# CANIso.net
KiCad netlist of a schematic drawn in EAGLE
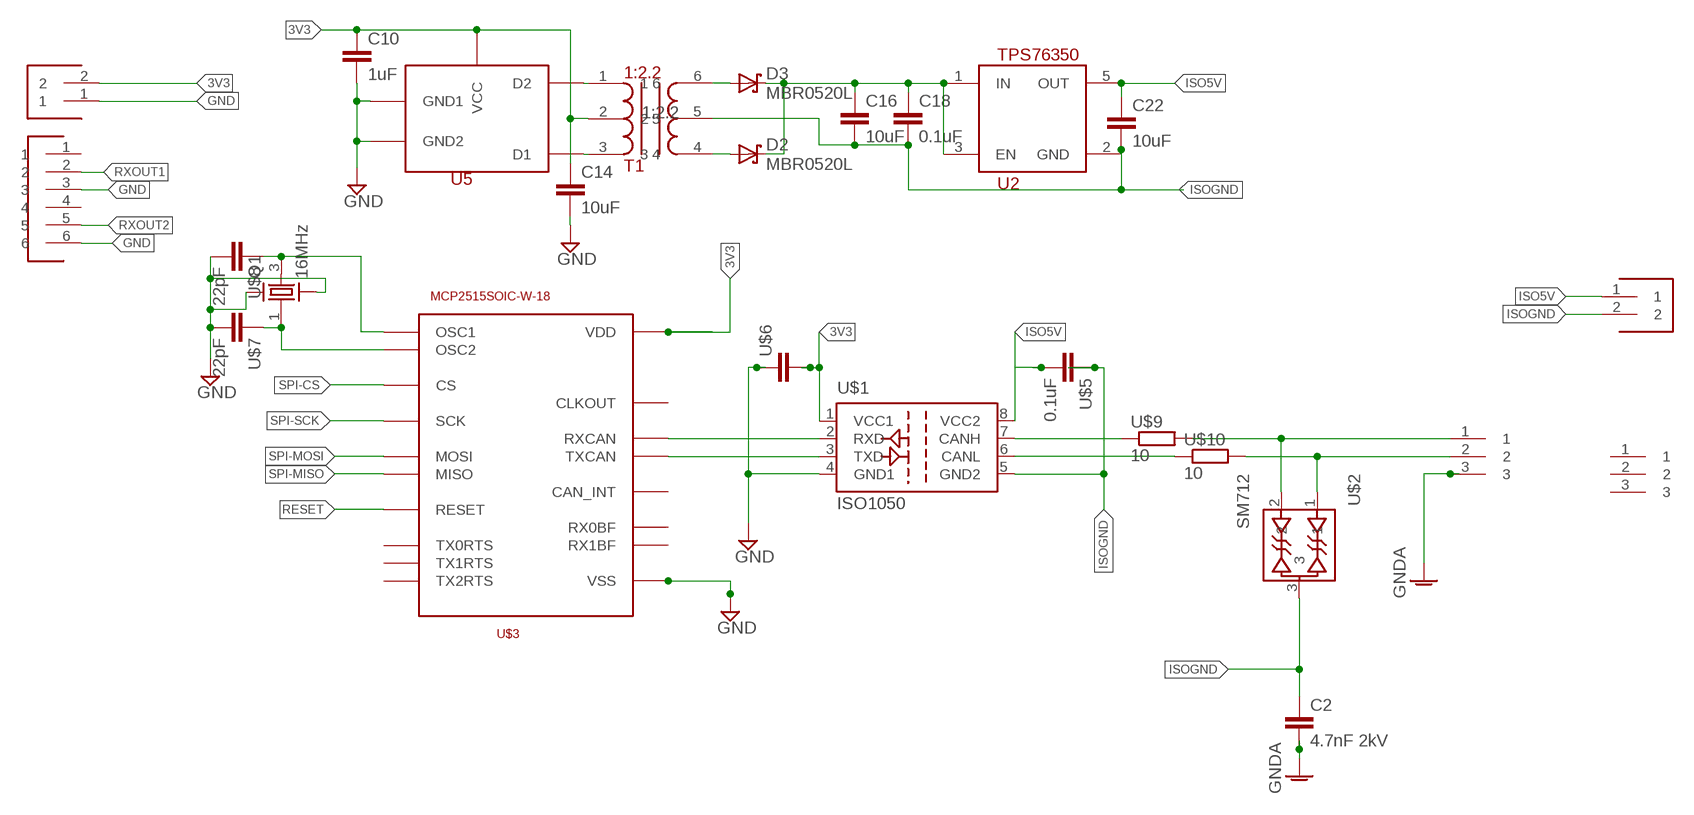
[diagram p0: schematic, sheet 1]

(export (version "E")
  (design (tool "Eeschema 10.0.6"))
  (components
    (comp (ref "C2")
      (value "4.7nF 2kV")
      (footprint "eagle-import:0805")
      (libsource (lib "eagle-import") (part "CAP0805"))
    )
    (comp (ref "C10")
      (value "1uF")
      (footprint "eagle-import:0805")
      (libsource (lib "eagle-import") (part "CAP0805"))
    )
    (comp (ref "C14")
      (value "10uF")
      (footprint "eagle-import:0805")
      (libsource (lib "eagle-import") (part "CAP0805"))
    )
    (comp (ref "C16")
      (value "10uF")
      (footprint "eagle-import:0805")
      (libsource (lib "eagle-import") (part "CAP0805"))
    )
    (comp (ref "C18")
      (value "0.1uF")
      (footprint "eagle-import:0805")
      (libsource (lib "eagle-import") (part "CAP0805"))
    )
    (comp (ref "C22")
      (value "10uF")
      (footprint "eagle-import:0805")
      (libsource (lib "eagle-import") (part "CAP0805"))
    )
    (comp (ref "D2")
      (value "MBR0520L")
      (footprint "eagle-import:SOD123")
      (libsource (lib "eagle-import") (part "MBR0520L"))
    )
    (comp (ref "D3")
      (value "MBR0520L")
      (footprint "eagle-import:SOD123")
      (libsource (lib "eagle-import") (part "MBR0520L"))
    )
    (comp (ref "J1")
      (value "CON-2STD-2.54")
      (footprint "eagle-import:CON-2")
      (libsource (lib "eagle-import") (part "CON-2STD-2.54"))
    )
    (comp (ref "J3")
      (value "CON-2STD-2.54")
      (footprint "eagle-import:CON-2")
      (libsource (lib "eagle-import") (part "CON-2STD-2.54"))
    )
    (comp (ref "J4")
      (value "CON-6")
      (footprint "eagle-import:CON-6")
      (libsource (lib "eagle-import") (part "CON-6"))
    )
    (comp (ref "Q1")
      (value "16MHz")
      (footprint "eagle-import:ABM3B")
      (libsource (lib "eagle-import") (part "ABM3B"))
    )
    (comp (ref "T1")
      (value "1:2.2")
      (footprint "eagle-import:WE_TRANSFORMER")
      (fields (field (name "TURNS") "1:2.2"))
      (libsource (lib "eagle-import") (part "WE-PP-ISO-TRANSFORMER760390013"))
    )
    (comp (ref "U$1")
      (value "ISO1050")
      (footprint "eagle-import:DUB")
      (libsource (lib "eagle-import") (part "ISO1050"))
    )
    (comp (ref "U$2")
      (value "SM712")
      (footprint "eagle-import:SOT23-3L")
      (libsource (lib "eagle-import") (part "SM712"))
    )
    (comp (ref "U$3")
      (value "MCP2515SOIC-W-18")
      (footprint "eagle-import:SOIC-W-18")
      (libsource (lib "eagle-import") (part "MCP2515SOIC-W-18"))
    )
    (comp (ref "U$4")
      (value "CON-3")
      (footprint "eagle-import:CON-3")
      (libsource (lib "eagle-import") (part "CON-3"))
    )
    (comp (ref "U$5")
      (value "0.1uF")
      (footprint "eagle-import:0805")
      (libsource (lib "eagle-import") (part "CAP0805"))
    )
    (comp (ref "U$6")
      (value "CAP0805")
      (footprint "eagle-import:0805")
      (libsource (lib "eagle-import") (part "CAP0805"))
    )
    (comp (ref "U$7")
      (value "22pF")
      (footprint "eagle-import:0805")
      (libsource (lib "eagle-import") (part "CAP0805"))
    )
    (comp (ref "U$8")
      (value "22pF")
      (footprint "eagle-import:0805")
      (libsource (lib "eagle-import") (part "CAP0805"))
    )
    (comp (ref "U$9")
      (value "10")
      (footprint "eagle-import:0805")
      (libsource (lib "eagle-import") (part "RES0805"))
    )
    (comp (ref "U$10")
      (value "10")
      (footprint "eagle-import:0805")
      (libsource (lib "eagle-import") (part "RES0805"))
    )
    (comp (ref "U$11")
      (value "CON-3")
      (footprint "eagle-import:CON-3")
      (libsource (lib "eagle-import") (part "CON-3"))
    )
    (comp (ref "U2")
      (value "TPS76350")
      (footprint "eagle-import:SOT23-5L")
      (libsource (lib "eagle-import") (part "TPS76350"))
    )
    (comp (ref "U5")
      (value "SN6501DBVT")
      (footprint "eagle-import:SOT23-5L")
      (libsource (lib "eagle-import") (part "SN6501DBVT"))
    )
  )
  (nets
    (net (code "1") (name "3V3") (class "Default")
      (node (ref "C10") (pin "1") (pinfunction "1_1") (pintype "passive"))
      (node (ref "C14") (pin "1") (pinfunction "1_1") (pintype "passive"))
      (node (ref "J1") (pin "2") (pinfunction "2_2") (pintype "bidirectional"))
      (node (ref "T1") (pin "2") (pinfunction "2_2") (pintype "input"))
      (node (ref "U$1") (pin "1") (pinfunction "VCC1_1") (pintype "power_in"))
      (node (ref "U$3") (pin "18") (pinfunction "VDD_18") (pintype "power_in"))
      (node (ref "U$6") (pin "2") (pinfunction "2_2") (pintype "passive"))
      (node (ref "U5") (pin "2") (pinfunction "VCC_2") (pintype "bidirectional"))
    )
    (net (code "2") (name "GND") (class "Default")
      (node (ref "C10") (pin "2") (pinfunction "2_2") (pintype "passive"))
      (node (ref "C14") (pin "2") (pinfunction "2_2") (pintype "passive"))
      (node (ref "J1") (pin "1") (pinfunction "1_1") (pintype "bidirectional"))
      (node (ref "J4") (pin "3") (pinfunction "3_3") (pintype "bidirectional"))
      (node (ref "J4") (pin "6") (pinfunction "6_6") (pintype "bidirectional"))
      (node (ref "Q1") (pin "2") (pinfunction "GND_2") (pintype "bidirectional"))
      (node (ref "Q1") (pin "4") (pinfunction "GND2_4") (pintype "bidirectional"))
      (node (ref "U$1") (pin "4") (pinfunction "GND1_4") (pintype "power_in"))
      (node (ref "U$3") (pin "9") (pinfunction "VSS_9") (pintype "power_in"))
      (node (ref "U$6") (pin "1") (pinfunction "1_1") (pintype "passive"))
      (node (ref "U$7") (pin "2") (pinfunction "2_2") (pintype "passive"))
      (node (ref "U$8") (pin "2") (pinfunction "2_2") (pintype "passive"))
      (node (ref "U5") (pin "4") (pinfunction "GND1_4") (pintype "bidirectional"))
      (node (ref "U5") (pin "5") (pinfunction "GND2_5") (pintype "bidirectional"))
    )
    (net (code "3") (name "GNDA") (class "Default")
      (node (ref "C2") (pin "2") (pinfunction "2_2") (pintype "passive"))
      (node (ref "U$4") (pin "3") (pinfunction "3_3") (pintype "bidirectional"))
    )
    (net (code "4") (name "ISO5V") (class "Default")
      (node (ref "C22") (pin "1") (pinfunction "1_1") (pintype "passive"))
      (node (ref "J3") (pin "1") (pinfunction "1_1") (pintype "bidirectional"))
      (node (ref "U$1") (pin "8") (pinfunction "VCC2_8") (pintype "power_in"))
      (node (ref "U2") (pin "5") (pinfunction "OUT_5") (pintype "bidirectional"))
    )
    (net (code "5") (name "ISOGND") (class "Default")
      (node (ref "C16") (pin "2") (pinfunction "2_2") (pintype "passive"))
      (node (ref "C18") (pin "2") (pinfunction "2_2") (pintype "passive"))
      (node (ref "C2") (pin "1") (pinfunction "1_1") (pintype "passive"))
      (node (ref "C22") (pin "2") (pinfunction "2_2") (pintype "passive"))
      (node (ref "J3") (pin "2") (pinfunction "2_2") (pintype "bidirectional"))
      (node (ref "T1") (pin "5") (pinfunction "5_5") (pintype "passive"))
      (node (ref "U$1") (pin "5") (pinfunction "GND2_5") (pintype "power_in"))
      (node (ref "U$2") (pin "3") (pinfunction "3_3") (pintype "output"))
      (node (ref "U$5") (pin "1") (pinfunction "1_1") (pintype "passive"))
      (node (ref "U2") (pin "2") (pinfunction "GND_2") (pintype "bidirectional"))
    )
    (net (code "6") (name "Net-(D2-PadA)") (class "Default")
      (node (ref "D2") (pin "A") (pinfunction "A_A") (pintype "passive"))
      (node (ref "T1") (pin "4") (pinfunction "4_4") (pintype "passive"))
    )
    (net (code "7") (name "Net-(D3-PadA)") (class "Default")
      (node (ref "D3") (pin "A") (pinfunction "A_A") (pintype "passive"))
      (node (ref "T1") (pin "6") (pinfunction "6_6") (pintype "passive"))
    )
    (net (code "8") (name "Net-(Q1-2)") (class "Default")
      (node (ref "Q1") (pin "3") (pinfunction "2_3") (pintype "passive"))
      (node (ref "U$3") (pin "8") (pinfunction "OSC1_8") (pintype "bidirectional"))
      (node (ref "U$8") (pin "1") (pinfunction "1_1") (pintype "passive"))
    )
    (net (code "9") (name "Net-(U$1-CANH)") (class "Default")
      (node (ref "U$1") (pin "7") (pinfunction "CANH_7") (pintype "output"))
      (node (ref "U$9") (pin "1") (pinfunction "1_1") (pintype "passive"))
    )
    (net (code "10") (name "Net-(U$1-CANL)") (class "Default")
      (node (ref "U$1") (pin "6") (pinfunction "CANL_6") (pintype "output"))
      (node (ref "U$10") (pin "1") (pinfunction "1_1") (pintype "passive"))
    )
    (net (code "11") (name "Net-(U$1-RXD)") (class "Default")
      (node (ref "U$1") (pin "2") (pinfunction "RXD_2") (pintype "input"))
      (node (ref "U$3") (pin "2") (pinfunction "RXCAN_2") (pintype "bidirectional"))
    )
    (net (code "12") (name "Net-(U$1-TXD)") (class "Default")
      (node (ref "U$1") (pin "3") (pinfunction "TXD_3") (pintype "input"))
      (node (ref "U$3") (pin "1") (pinfunction "TXCAN_1") (pintype "bidirectional"))
    )
    (net (code "13") (name "Net-(U$2-Pad2)") (class "Default")
      (node (ref "U$2") (pin "2") (pinfunction "2_2") (pintype "input"))
      (node (ref "U$4") (pin "1") (pinfunction "1_1") (pintype "bidirectional"))
      (node (ref "U$9") (pin "2") (pinfunction "2_2") (pintype "passive"))
    )
    (net (code "14") (name "Net-(U$3-OSC2)") (class "Default")
      (node (ref "Q1") (pin "1") (pinfunction "1_1") (pintype "passive"))
      (node (ref "U$3") (pin "7") (pinfunction "OSC2_7") (pintype "bidirectional"))
      (node (ref "U$7") (pin "1") (pinfunction "1_1") (pintype "passive"))
    )
    (net (code "15") (name "Net-(U$10-Pad2)") (class "Default")
      (node (ref "U$10") (pin "2") (pinfunction "2_2") (pintype "passive"))
      (node (ref "U$2") (pin "1") (pinfunction "1_1") (pintype "input"))
      (node (ref "U$4") (pin "2") (pinfunction "2_2") (pintype "bidirectional"))
    )
    (net (code "16") (name "Net-(U2-EN)") (class "Default")
      (node (ref "C16") (pin "1") (pinfunction "1_1") (pintype "passive"))
      (node (ref "C18") (pin "1") (pinfunction "1_1") (pintype "passive"))
      (node (ref "D2") (pin "C") (pinfunction "C_C") (pintype "passive"))
      (node (ref "D3") (pin "C") (pinfunction "C_C") (pintype "passive"))
      (node (ref "U2") (pin "1") (pinfunction "IN_1") (pintype "bidirectional"))
      (node (ref "U2") (pin "3") (pinfunction "EN_3") (pintype "bidirectional"))
    )
    (net (code "17") (name "Net-(U5-D1)") (class "Default")
      (node (ref "T1") (pin "3") (pinfunction "3_3") (pintype "input"))
      (node (ref "U5") (pin "1") (pinfunction "D1_1") (pintype "bidirectional"))
    )
    (net (code "18") (name "Net-(U5-D2)") (class "Default")
      (node (ref "T1") (pin "1") (pinfunction "1_1") (pintype "input"))
      (node (ref "U5") (pin "3") (pinfunction "D2_3") (pintype "bidirectional"))
    )
    (net (code "19") (name "RESET") (class "Default")
      (node (ref "U$3") (pin "17") (pinfunction "RESET_17") (pintype "bidirectional"))
    )
    (net (code "20") (name "RXOUT1") (class "Default")
      (node (ref "J4") (pin "2") (pinfunction "2_2") (pintype "bidirectional"))
    )
    (net (code "21") (name "RXOUT2") (class "Default")
      (node (ref "J4") (pin "5") (pinfunction "5_5") (pintype "bidirectional"))
    )
    (net (code "22") (name "SPI-CS") (class "Default")
      (node (ref "U$3") (pin "16") (pinfunction "CS_16") (pintype "bidirectional"))
    )
    (net (code "23") (name "SPI-MISO") (class "Default")
      (node (ref "U$3") (pin "15") (pinfunction "MISO_15") (pintype "bidirectional"))
    )
    (net (code "24") (name "SPI-MOSI") (class "Default")
      (node (ref "U$3") (pin "14") (pinfunction "MOSI_14") (pintype "bidirectional"))
    )
    (net (code "25") (name "SPI-SCK") (class "Default")
      (node (ref "U$3") (pin "13") (pinfunction "SCK_13") (pintype "bidirectional"))
    )
    (net (code "26") (name "unconnected-(J4-Pad1)") (class "Default")
      (node (ref "J4") (pin "1") (pinfunction "1_1") (pintype "bidirectional"))
    )
    (net (code "27") (name "unconnected-(J4-Pad4)") (class "Default")
      (node (ref "J4") (pin "4") (pinfunction "4_4") (pintype "bidirectional"))
    )
    (net (code "28") (name "unconnected-(U$3-CAN_INT-Pad12)") (class "Default")
      (node (ref "U$3") (pin "12") (pinfunction "CAN_INT_12") (pintype "bidirectional"))
    )
    (net (code "29") (name "unconnected-(U$3-CLKOUT-Pad3)") (class "Default")
      (node (ref "U$3") (pin "3") (pinfunction "CLKOUT_3") (pintype "bidirectional"))
    )
    (net (code "30") (name "unconnected-(U$3-RX0BF-Pad11)") (class "Default")
      (node (ref "U$3") (pin "11") (pinfunction "RX0BF_11") (pintype "bidirectional"))
    )
    (net (code "31") (name "unconnected-(U$3-RX1BF-Pad10)") (class "Default")
      (node (ref "U$3") (pin "10") (pinfunction "RX1BF_10") (pintype "bidirectional"))
    )
    (net (code "32") (name "unconnected-(U$3-TX0RTS-Pad4)") (class "Default")
      (node (ref "U$3") (pin "4") (pinfunction "TX0RTS_4") (pintype "bidirectional"))
    )
    (net (code "33") (name "unconnected-(U$3-TX1RTS-Pad5)") (class "Default")
      (node (ref "U$3") (pin "5") (pinfunction "TX1RTS_5") (pintype "bidirectional"))
    )
    (net (code "34") (name "unconnected-(U$3-TX2RTS-Pad6)") (class "Default")
      (node (ref "U$3") (pin "6") (pinfunction "TX2RTS_6") (pintype "bidirectional"))
    )
    (net (code "35") (name "unconnected-(U$5-Pad2)") (class "Default")
      (node (ref "U$5") (pin "2") (pinfunction "2_2") (pintype "passive"))
    )
    (net (code "36") (name "unconnected-(U$11-Pad1)") (class "Default")
      (node (ref "U$11") (pin "1") (pinfunction "1_1") (pintype "bidirectional"))
    )
    (net (code "37") (name "unconnected-(U$11-Pad2)") (class "Default")
      (node (ref "U$11") (pin "2") (pinfunction "2_2") (pintype "bidirectional"))
    )
    (net (code "38") (name "unconnected-(U$11-Pad3)") (class "Default")
      (node (ref "U$11") (pin "3") (pinfunction "3_3") (pintype "bidirectional"))
    )
  )
)
